# LCs.net
KiCad netlist of a schematic drawn in Altium Designer
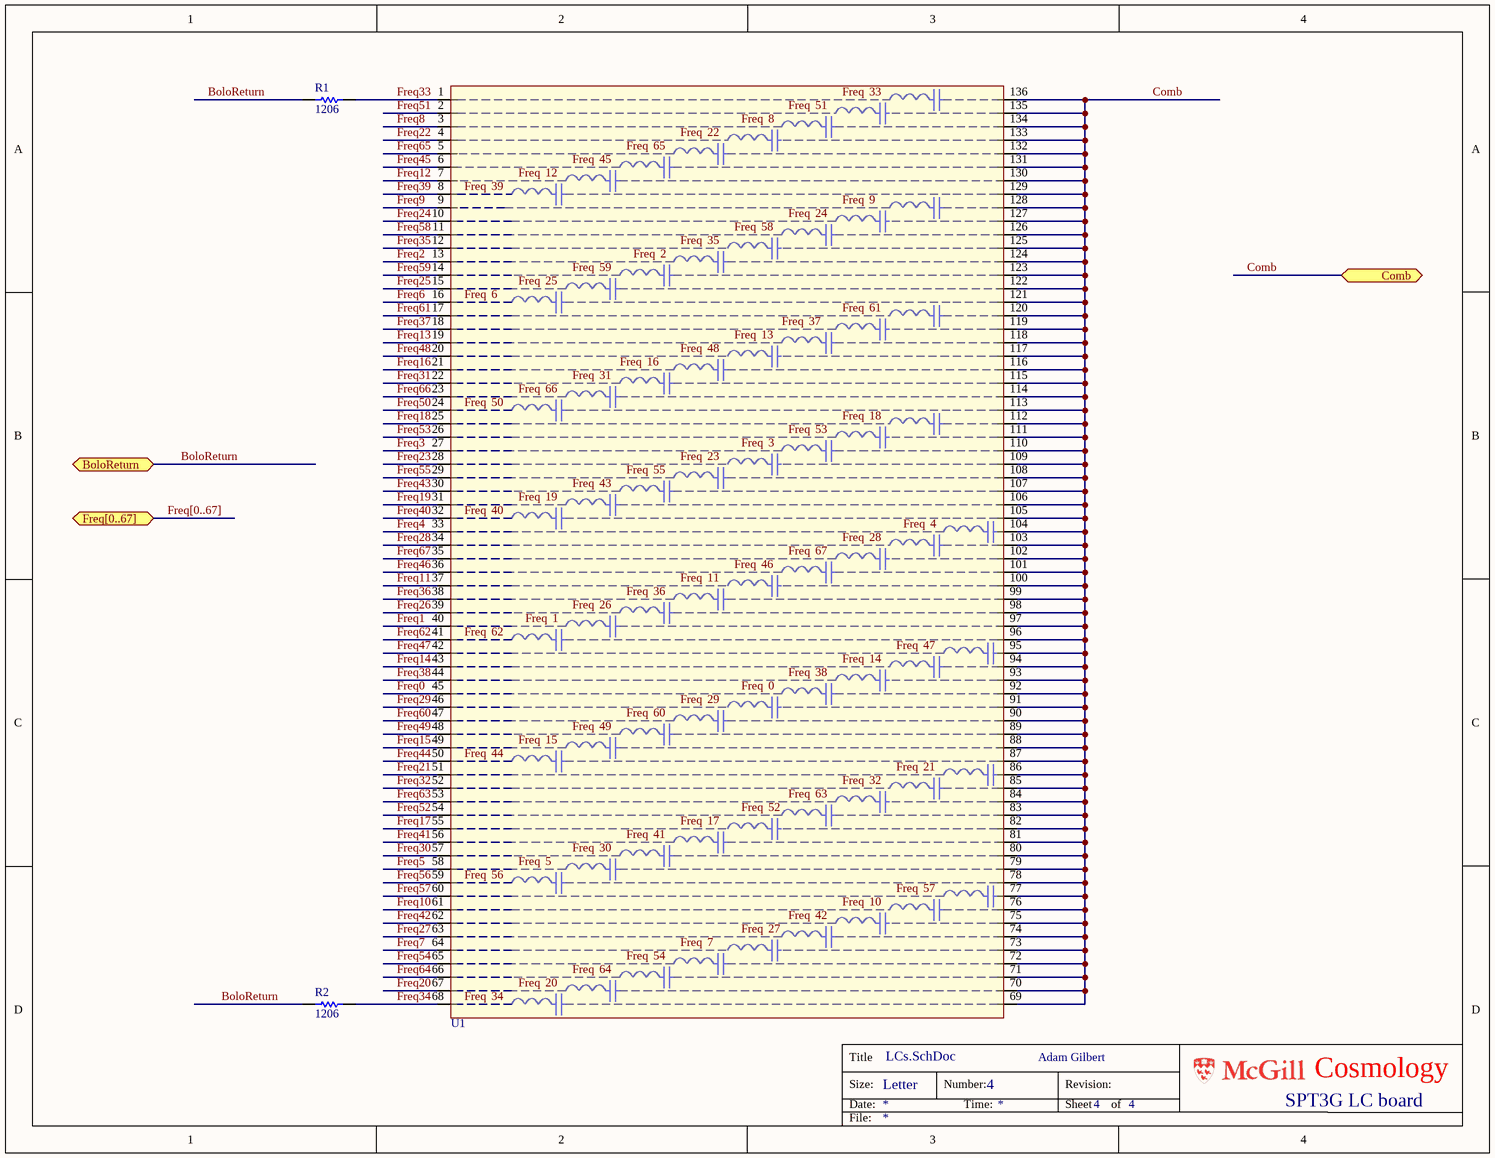
[diagram p0: LCs.SchDoc]

(export (version "E")
  (design (tool "Eeschema 10.0.6"))
  (components
    (comp (ref "R1")
      (value "Res1206")
      (footprint "1206")
      (description "Resistor")
      (libsource (lib "SPT3G_LCBoard") (part "Res1206"))
    )
    (comp (ref "R2")
      (value "Res1206")
      (footprint "1206")
      (description "Resistor")
      (libsource (lib "SPT3G_LCBoard") (part "Res1206"))
    )
    (comp (ref "U1")
      (value "LC68_wafer")
      (footprint "68xLC")
      (description "Gold bonded integrated LC")
      (libsource (lib "SPT3G_LCBoard") (part "LC68Wafer"))
    )
  )
  (nets
    (net (code "1") (name "/BoloReturn") (class "Default")
      (node (ref "R1") (pin "1") (pinfunction "1_1") (pintype "passive"))
      (node (ref "R2") (pin "1") (pinfunction "1_1") (pintype "passive"))
    )
    (net (code "2") (name "/Comb") (class "Default")
      (node (ref "U1") (pin "100") (pinfunction "100_100") (pintype "passive"))
      (node (ref "U1") (pin "101") (pinfunction "101_101") (pintype "passive"))
      (node (ref "U1") (pin "102") (pinfunction "102_102") (pintype "passive"))
      (node (ref "U1") (pin "103") (pinfunction "103_103") (pintype "passive"))
      (node (ref "U1") (pin "104") (pinfunction "104_104") (pintype "passive"))
      (node (ref "U1") (pin "105") (pinfunction "105_105") (pintype "passive"))
      (node (ref "U1") (pin "106") (pinfunction "106_106") (pintype "passive"))
      (node (ref "U1") (pin "107") (pinfunction "107_107") (pintype "passive"))
      (node (ref "U1") (pin "108") (pinfunction "108_108") (pintype "passive"))
      (node (ref "U1") (pin "109") (pinfunction "109_109") (pintype "passive"))
      (node (ref "U1") (pin "110") (pinfunction "110_110") (pintype "passive"))
      (node (ref "U1") (pin "111") (pinfunction "111_111") (pintype "passive"))
      (node (ref "U1") (pin "112") (pinfunction "112_112") (pintype "passive"))
      (node (ref "U1") (pin "113") (pinfunction "113_113") (pintype "passive"))
      (node (ref "U1") (pin "114") (pinfunction "114_114") (pintype "passive"))
      (node (ref "U1") (pin "115") (pinfunction "115_115") (pintype "passive"))
      (node (ref "U1") (pin "116") (pinfunction "116_116") (pintype "passive"))
      (node (ref "U1") (pin "117") (pinfunction "117_117") (pintype "passive"))
      (node (ref "U1") (pin "118") (pinfunction "118_118") (pintype "passive"))
      (node (ref "U1") (pin "119") (pinfunction "119_119") (pintype "passive"))
      (node (ref "U1") (pin "120") (pinfunction "120_120") (pintype "passive"))
      (node (ref "U1") (pin "121") (pinfunction "121_121") (pintype "passive"))
      (node (ref "U1") (pin "122") (pinfunction "122_122") (pintype "passive"))
      (node (ref "U1") (pin "123") (pinfunction "123_123") (pintype "passive"))
      (node (ref "U1") (pin "124") (pinfunction "124_124") (pintype "passive"))
      (node (ref "U1") (pin "125") (pinfunction "125_125") (pintype "passive"))
      (node (ref "U1") (pin "126") (pinfunction "126_126") (pintype "passive"))
      (node (ref "U1") (pin "127") (pinfunction "127_127") (pintype "passive"))
      (node (ref "U1") (pin "128") (pinfunction "128_128") (pintype "passive"))
      (node (ref "U1") (pin "129") (pinfunction "129_129") (pintype "passive"))
      (node (ref "U1") (pin "130") (pinfunction "130_130") (pintype "passive"))
      (node (ref "U1") (pin "131") (pinfunction "131_131") (pintype "passive"))
      (node (ref "U1") (pin "132") (pinfunction "132_132") (pintype "passive"))
      (node (ref "U1") (pin "133") (pinfunction "133_133") (pintype "passive"))
      (node (ref "U1") (pin "134") (pinfunction "134_134") (pintype "passive"))
      (node (ref "U1") (pin "135") (pinfunction "135_135") (pintype "passive"))
      (node (ref "U1") (pin "136") (pinfunction "136_136") (pintype "passive"))
      (node (ref "U1") (pin "69") (pinfunction "69_69") (pintype "passive"))
      (node (ref "U1") (pin "70") (pinfunction "70_70") (pintype "passive"))
      (node (ref "U1") (pin "71") (pinfunction "71_71") (pintype "passive"))
      (node (ref "U1") (pin "72") (pinfunction "72_72") (pintype "passive"))
      (node (ref "U1") (pin "73") (pinfunction "73_73") (pintype "passive"))
      (node (ref "U1") (pin "74") (pinfunction "74_74") (pintype "passive"))
      (node (ref "U1") (pin "75") (pinfunction "75_75") (pintype "passive"))
      (node (ref "U1") (pin "76") (pinfunction "76_76") (pintype "passive"))
      (node (ref "U1") (pin "77") (pinfunction "77_77") (pintype "passive"))
      (node (ref "U1") (pin "78") (pinfunction "78_78") (pintype "passive"))
      (node (ref "U1") (pin "79") (pinfunction "79_79") (pintype "passive"))
      (node (ref "U1") (pin "80") (pinfunction "80_80") (pintype "passive"))
      (node (ref "U1") (pin "81") (pinfunction "81_81") (pintype "passive"))
      (node (ref "U1") (pin "82") (pinfunction "82_82") (pintype "passive"))
      (node (ref "U1") (pin "83") (pinfunction "83_83") (pintype "passive"))
      (node (ref "U1") (pin "84") (pinfunction "84_84") (pintype "passive"))
      (node (ref "U1") (pin "85") (pinfunction "85_85") (pintype "passive"))
      (node (ref "U1") (pin "86") (pinfunction "86_86") (pintype "passive"))
      (node (ref "U1") (pin "87") (pinfunction "87_87") (pintype "passive"))
      (node (ref "U1") (pin "88") (pinfunction "88_88") (pintype "passive"))
      (node (ref "U1") (pin "89") (pinfunction "89_89") (pintype "passive"))
      (node (ref "U1") (pin "90") (pinfunction "90_90") (pintype "passive"))
      (node (ref "U1") (pin "91") (pinfunction "91_91") (pintype "passive"))
      (node (ref "U1") (pin "92") (pinfunction "92_92") (pintype "passive"))
      (node (ref "U1") (pin "93") (pinfunction "93_93") (pintype "passive"))
      (node (ref "U1") (pin "94") (pinfunction "94_94") (pintype "passive"))
      (node (ref "U1") (pin "95") (pinfunction "95_95") (pintype "passive"))
      (node (ref "U1") (pin "96") (pinfunction "96_96") (pintype "passive"))
      (node (ref "U1") (pin "97") (pinfunction "97_97") (pintype "passive"))
      (node (ref "U1") (pin "98") (pinfunction "98_98") (pintype "passive"))
      (node (ref "U1") (pin "99") (pinfunction "99_99") (pintype "passive"))
    )
    (net (code "3") (name "/Freq0") (class "Default")
      (node (ref "U1") (pin "45") (pinfunction "45_45") (pintype "passive"))
    )
    (net (code "4") (name "/Freq1") (class "Default")
      (node (ref "U1") (pin "40") (pinfunction "40_40") (pintype "passive"))
    )
    (net (code "5") (name "/Freq2") (class "Default")
      (node (ref "U1") (pin "13") (pinfunction "13_13") (pintype "passive"))
    )
    (net (code "6") (name "/Freq3") (class "Default")
      (node (ref "U1") (pin "27") (pinfunction "27_27") (pintype "passive"))
    )
    (net (code "7") (name "/Freq4") (class "Default")
      (node (ref "U1") (pin "33") (pinfunction "33_33") (pintype "passive"))
    )
    (net (code "8") (name "/Freq5") (class "Default")
      (node (ref "U1") (pin "58") (pinfunction "58_58") (pintype "passive"))
    )
    (net (code "9") (name "/Freq6") (class "Default")
      (node (ref "U1") (pin "16") (pinfunction "16_16") (pintype "passive"))
    )
    (net (code "10") (name "/Freq7") (class "Default")
      (node (ref "U1") (pin "64") (pinfunction "64_64") (pintype "passive"))
    )
    (net (code "11") (name "/Freq8") (class "Default")
      (node (ref "U1") (pin "3") (pinfunction "3_3") (pintype "passive"))
    )
    (net (code "12") (name "/Freq9") (class "Default")
      (node (ref "U1") (pin "9") (pinfunction "9_9") (pintype "passive"))
    )
    (net (code "13") (name "/Freq10") (class "Default")
      (node (ref "U1") (pin "61") (pinfunction "61_61") (pintype "passive"))
    )
    (net (code "14") (name "/Freq11") (class "Default")
      (node (ref "U1") (pin "37") (pinfunction "37_37") (pintype "passive"))
    )
    (net (code "15") (name "/Freq12") (class "Default")
      (node (ref "U1") (pin "7") (pinfunction "7_7") (pintype "passive"))
    )
    (net (code "16") (name "/Freq13") (class "Default")
      (node (ref "U1") (pin "19") (pinfunction "19_19") (pintype "passive"))
    )
    (net (code "17") (name "/Freq14") (class "Default")
      (node (ref "U1") (pin "43") (pinfunction "43_43") (pintype "passive"))
    )
    (net (code "18") (name "/Freq15") (class "Default")
      (node (ref "U1") (pin "49") (pinfunction "49_49") (pintype "passive"))
    )
    (net (code "19") (name "/Freq16") (class "Default")
      (node (ref "U1") (pin "21") (pinfunction "21_21") (pintype "passive"))
    )
    (net (code "20") (name "/Freq17") (class "Default")
      (node (ref "U1") (pin "55") (pinfunction "55_55") (pintype "passive"))
    )
    (net (code "21") (name "/Freq18") (class "Default")
      (node (ref "U1") (pin "25") (pinfunction "25_25") (pintype "passive"))
    )
    (net (code "22") (name "/Freq19") (class "Default")
      (node (ref "U1") (pin "31") (pinfunction "31_31") (pintype "passive"))
    )
    (net (code "23") (name "/Freq20") (class "Default")
      (node (ref "U1") (pin "67") (pinfunction "67_67") (pintype "passive"))
    )
    (net (code "24") (name "/Freq21") (class "Default")
      (node (ref "U1") (pin "51") (pinfunction "51_51") (pintype "passive"))
    )
    (net (code "25") (name "/Freq22") (class "Default")
      (node (ref "U1") (pin "4") (pinfunction "4_4") (pintype "passive"))
    )
    (net (code "26") (name "/Freq23") (class "Default")
      (node (ref "U1") (pin "28") (pinfunction "28_28") (pintype "passive"))
    )
    (net (code "27") (name "/Freq24") (class "Default")
      (node (ref "U1") (pin "10") (pinfunction "10_10") (pintype "passive"))
    )
    (net (code "28") (name "/Freq25") (class "Default")
      (node (ref "U1") (pin "15") (pinfunction "15_15") (pintype "passive"))
    )
    (net (code "29") (name "/Freq26") (class "Default")
      (node (ref "U1") (pin "39") (pinfunction "39_39") (pintype "passive"))
    )
    (net (code "30") (name "/Freq27") (class "Default")
      (node (ref "U1") (pin "63") (pinfunction "63_63") (pintype "passive"))
    )
    (net (code "31") (name "/Freq28") (class "Default")
      (node (ref "U1") (pin "34") (pinfunction "34_34") (pintype "passive"))
    )
    (net (code "32") (name "/Freq29") (class "Default")
      (node (ref "U1") (pin "46") (pinfunction "46_46") (pintype "passive"))
    )
    (net (code "33") (name "/Freq30") (class "Default")
      (node (ref "U1") (pin "57") (pinfunction "57_57") (pintype "passive"))
    )
    (net (code "34") (name "/Freq31") (class "Default")
      (node (ref "U1") (pin "22") (pinfunction "22_22") (pintype "passive"))
    )
    (net (code "35") (name "/Freq32") (class "Default")
      (node (ref "U1") (pin "52") (pinfunction "52_52") (pintype "passive"))
    )
    (net (code "36") (name "/Freq33") (class "Default")
      (node (ref "R1") (pin "2") (pinfunction "2_2") (pintype "passive"))
      (node (ref "U1") (pin "1") (pinfunction "1_1") (pintype "passive"))
    )
    (net (code "37") (name "/Freq34") (class "Default")
      (node (ref "R2") (pin "2") (pinfunction "2_2") (pintype "passive"))
      (node (ref "U1") (pin "68") (pinfunction "68_68") (pintype "passive"))
    )
    (net (code "38") (name "/Freq35") (class "Default")
      (node (ref "U1") (pin "12") (pinfunction "12_12") (pintype "passive"))
    )
    (net (code "39") (name "/Freq36") (class "Default")
      (node (ref "U1") (pin "38") (pinfunction "38_38") (pintype "passive"))
    )
    (net (code "40") (name "/Freq37") (class "Default")
      (node (ref "U1") (pin "18") (pinfunction "18_18") (pintype "passive"))
    )
    (net (code "41") (name "/Freq38") (class "Default")
      (node (ref "U1") (pin "44") (pinfunction "44_44") (pintype "passive"))
    )
    (net (code "42") (name "/Freq39") (class "Default")
      (node (ref "U1") (pin "8") (pinfunction "8_8") (pintype "passive"))
    )
    (net (code "43") (name "/Freq40") (class "Default")
      (node (ref "U1") (pin "32") (pinfunction "32_32") (pintype "passive"))
    )
    (net (code "44") (name "/Freq41") (class "Default")
      (node (ref "U1") (pin "56") (pinfunction "56_56") (pintype "passive"))
    )
    (net (code "45") (name "/Freq42") (class "Default")
      (node (ref "U1") (pin "62") (pinfunction "62_62") (pintype "passive"))
    )
    (net (code "46") (name "/Freq43") (class "Default")
      (node (ref "U1") (pin "30") (pinfunction "30_30") (pintype "passive"))
    )
    (net (code "47") (name "/Freq44") (class "Default")
      (node (ref "U1") (pin "50") (pinfunction "50_50") (pintype "passive"))
    )
    (net (code "48") (name "/Freq45") (class "Default")
      (node (ref "U1") (pin "6") (pinfunction "6_6") (pintype "passive"))
    )
    (net (code "49") (name "/Freq46") (class "Default")
      (node (ref "U1") (pin "36") (pinfunction "36_36") (pintype "passive"))
    )
    (net (code "50") (name "/Freq47") (class "Default")
      (node (ref "U1") (pin "42") (pinfunction "42_42") (pintype "passive"))
    )
    (net (code "51") (name "/Freq48") (class "Default")
      (node (ref "U1") (pin "20") (pinfunction "20_20") (pintype "passive"))
    )
    (net (code "52") (name "/Freq49") (class "Default")
      (node (ref "U1") (pin "48") (pinfunction "48_48") (pintype "passive"))
    )
    (net (code "53") (name "/Freq50") (class "Default")
      (node (ref "U1") (pin "24") (pinfunction "24_24") (pintype "passive"))
    )
    (net (code "54") (name "/Freq51") (class "Default")
      (node (ref "U1") (pin "2") (pinfunction "2_2") (pintype "passive"))
    )
    (net (code "55") (name "/Freq52") (class "Default")
      (node (ref "U1") (pin "54") (pinfunction "54_54") (pintype "passive"))
    )
    (net (code "56") (name "/Freq53") (class "Default")
      (node (ref "U1") (pin "26") (pinfunction "26_26") (pintype "passive"))
    )
    (net (code "57") (name "/Freq54") (class "Default")
      (node (ref "U1") (pin "65") (pinfunction "65_65") (pintype "passive"))
    )
    (net (code "58") (name "/Freq55") (class "Default")
      (node (ref "U1") (pin "29") (pinfunction "29_29") (pintype "passive"))
    )
    (net (code "59") (name "/Freq56") (class "Default")
      (node (ref "U1") (pin "59") (pinfunction "59_59") (pintype "passive"))
    )
    (net (code "60") (name "/Freq57") (class "Default")
      (node (ref "U1") (pin "60") (pinfunction "60_60") (pintype "passive"))
    )
    (net (code "61") (name "/Freq58") (class "Default")
      (node (ref "U1") (pin "11") (pinfunction "11_11") (pintype "passive"))
    )
    (net (code "62") (name "/Freq59") (class "Default")
      (node (ref "U1") (pin "14") (pinfunction "14_14") (pintype "passive"))
    )
    (net (code "63") (name "/Freq60") (class "Default")
      (node (ref "U1") (pin "47") (pinfunction "47_47") (pintype "passive"))
    )
    (net (code "64") (name "/Freq61") (class "Default")
      (node (ref "U1") (pin "17") (pinfunction "17_17") (pintype "passive"))
    )
    (net (code "65") (name "/Freq62") (class "Default")
      (node (ref "U1") (pin "41") (pinfunction "41_41") (pintype "passive"))
    )
    (net (code "66") (name "/Freq63") (class "Default")
      (node (ref "U1") (pin "53") (pinfunction "53_53") (pintype "passive"))
    )
    (net (code "67") (name "/Freq64") (class "Default")
      (node (ref "U1") (pin "66") (pinfunction "66_66") (pintype "passive"))
    )
    (net (code "68") (name "/Freq65") (class "Default")
      (node (ref "U1") (pin "5") (pinfunction "5_5") (pintype "passive"))
    )
    (net (code "69") (name "/Freq66") (class "Default")
      (node (ref "U1") (pin "23") (pinfunction "23_23") (pintype "passive"))
    )
    (net (code "70") (name "/Freq67") (class "Default")
      (node (ref "U1") (pin "35") (pinfunction "35_35") (pintype "passive"))
    )
  )
)
